# BlueTooth.net
KiCad netlist of a schematic drawn in Altium Designer
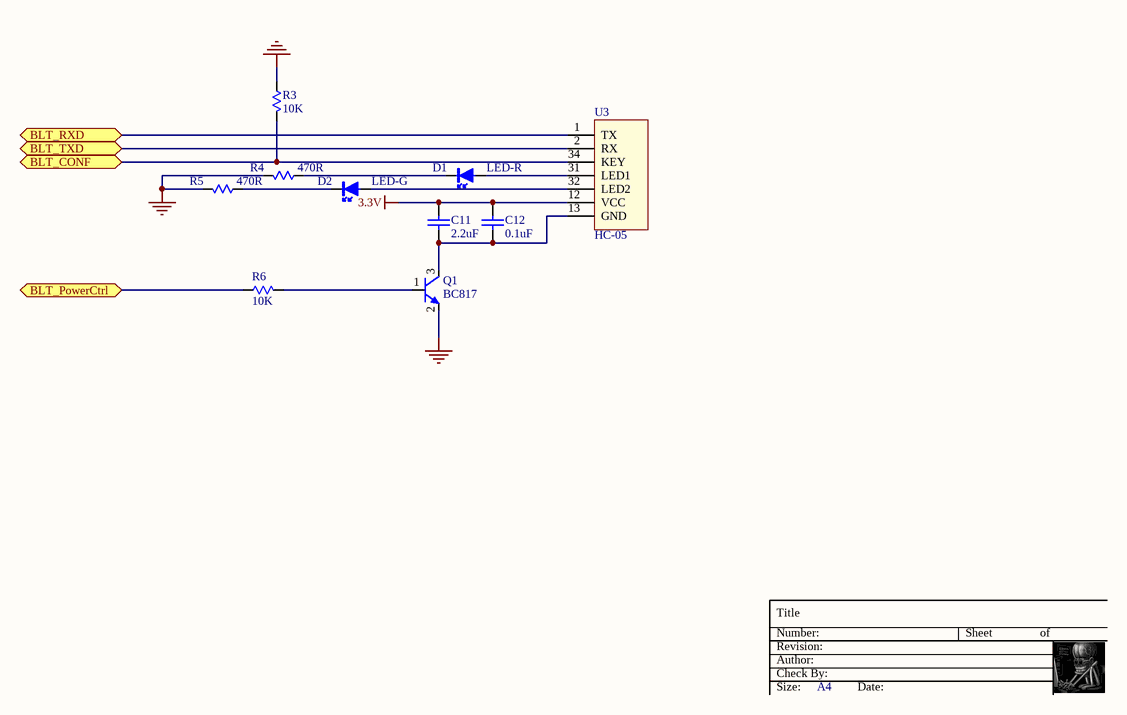
[diagram p0: BlueTooth.SchDoc]

(export (version "E")
  (design (tool "Eeschema 10.0.6"))
  (components
    (comp (ref "C11")
      (value "2.2uF")
      (footprint "C0603-S")
      (description "Capacitor")
      (libsource (lib "Passive Components Class") (part "CAP"))
    )
    (comp (ref "C12")
      (value "0.1uF")
      (footprint "C0603-S")
      (description "Capacitor")
      (libsource (lib "Passive Components Class") (part "CAP"))
    )
    (comp (ref "D1")
      (value "LED-R")
      (footprint "LED0603")
      (description "Light Emitting Diode")
      (libsource (lib "Passive Components Class") (part "LED"))
    )
    (comp (ref "D2")
      (value "LED-G")
      (footprint "LED0603")
      (description "Light Emitting Diode")
      (libsource (lib "Passive Components Class") (part "LED"))
    )
    (comp (ref "Q1")
      (value "BC817")
      (footprint "SOT-23")
      (description "NPN General Purpose Amplifier")
      (libsource (lib "Passive Components Class") (part "NPN"))
    )
    (comp (ref "R3")
      (value "10K")
      (footprint "R0603-S")
      (description "Resistor")
      (libsource (lib "Passive Components Class") (part "RES"))
    )
    (comp (ref "R4")
      (value "470R")
      (footprint "R0603-S")
      (description "Resistor")
      (libsource (lib "Passive Components Class") (part "RES"))
    )
    (comp (ref "R5")
      (value "470R")
      (footprint "R0603-S")
      (description "Resistor")
      (libsource (lib "Passive Components Class") (part "RES"))
    )
    (comp (ref "R6")
      (value "10K")
      (footprint "R0603-S")
      (description "Resistor")
      (libsource (lib "Passive Components Class") (part "RES"))
    )
    (comp (ref "U3")
      (value "HC-05")
      (footprint "HC-05")
      (description "Bluetooth Module")
      (libsource (lib "RF Class") (part "HC-05"))
    )
  )
  (nets
    (net (code "1") (name "/BLT_CONF") (class "Default")
      (node (ref "R3") (pin "1") (pinfunction "1_1") (pintype "passive"))
      (node (ref "U3") (pin "34") (pinfunction "KEY_34") (pintype "passive"))
    )
    (net (code "2") (name "/BLT_PowerCtrl") (class "Default")
      (node (ref "R6") (pin "2") (pinfunction "2_2") (pintype "passive"))
    )
    (net (code "3") (name "/BLT_RXD") (class "Default")
      (node (ref "U3") (pin "1") (pinfunction "TX_1") (pintype "passive"))
    )
    (net (code "4") (name "/BLT_TXD") (class "Default")
      (node (ref "U3") (pin "2") (pinfunction "RX_2") (pintype "passive"))
    )
    (net (code "5") (name "3.3V") (class "Default")
      (node (ref "C11") (pin "2") (pinfunction "2_2") (pintype "passive"))
      (node (ref "C12") (pin "2") (pinfunction "2_2") (pintype "passive"))
      (node (ref "U3") (pin "12") (pinfunction "VCC_12") (pintype "passive"))
    )
    (net (code "6") (name "GND") (class "Default")
      (node (ref "Q1") (pin "2") (pinfunction "E_2") (pintype "passive"))
      (node (ref "R3") (pin "2") (pinfunction "2_2") (pintype "passive"))
      (node (ref "R4") (pin "1") (pinfunction "1_1") (pintype "passive"))
      (node (ref "R5") (pin "1") (pinfunction "1_1") (pintype "passive"))
    )
    (net (code "7") (name "Net-(D1-A)") (class "Default")
      (node (ref "D1") (pin "1") (pinfunction "A_1") (pintype "passive"))
      (node (ref "U3") (pin "31") (pinfunction "LED1_31") (pintype "passive"))
    )
    (net (code "8") (name "Net-(D1-K)") (class "Default")
      (node (ref "D1") (pin "2") (pinfunction "K_2") (pintype "passive"))
      (node (ref "R4") (pin "2") (pinfunction "2_2") (pintype "passive"))
    )
    (net (code "9") (name "Net-(D2-A)") (class "Default")
      (node (ref "D2") (pin "1") (pinfunction "A_1") (pintype "passive"))
      (node (ref "U3") (pin "32") (pinfunction "LED2_32") (pintype "passive"))
    )
    (net (code "10") (name "Net-(D2-K)") (class "Default")
      (node (ref "D2") (pin "2") (pinfunction "K_2") (pintype "passive"))
      (node (ref "R5") (pin "2") (pinfunction "2_2") (pintype "passive"))
    )
    (net (code "11") (name "Net-(Q1-B)") (class "Default")
      (node (ref "Q1") (pin "1") (pinfunction "B_1") (pintype "passive"))
      (node (ref "R6") (pin "1") (pinfunction "1_1") (pintype "passive"))
    )
    (net (code "12") (name "Net-(Q1-C)") (class "Default")
      (node (ref "C11") (pin "1") (pinfunction "1_1") (pintype "passive"))
      (node (ref "C12") (pin "1") (pinfunction "1_1") (pintype "passive"))
      (node (ref "Q1") (pin "3") (pinfunction "C_3") (pintype "passive"))
      (node (ref "U3") (pin "13") (pinfunction "GND_13") (pintype "passive"))
    )
  )
)
